# AnalogInputModule2_r1_0.net
KiCad netlist of a schematic drawn in EAGLE
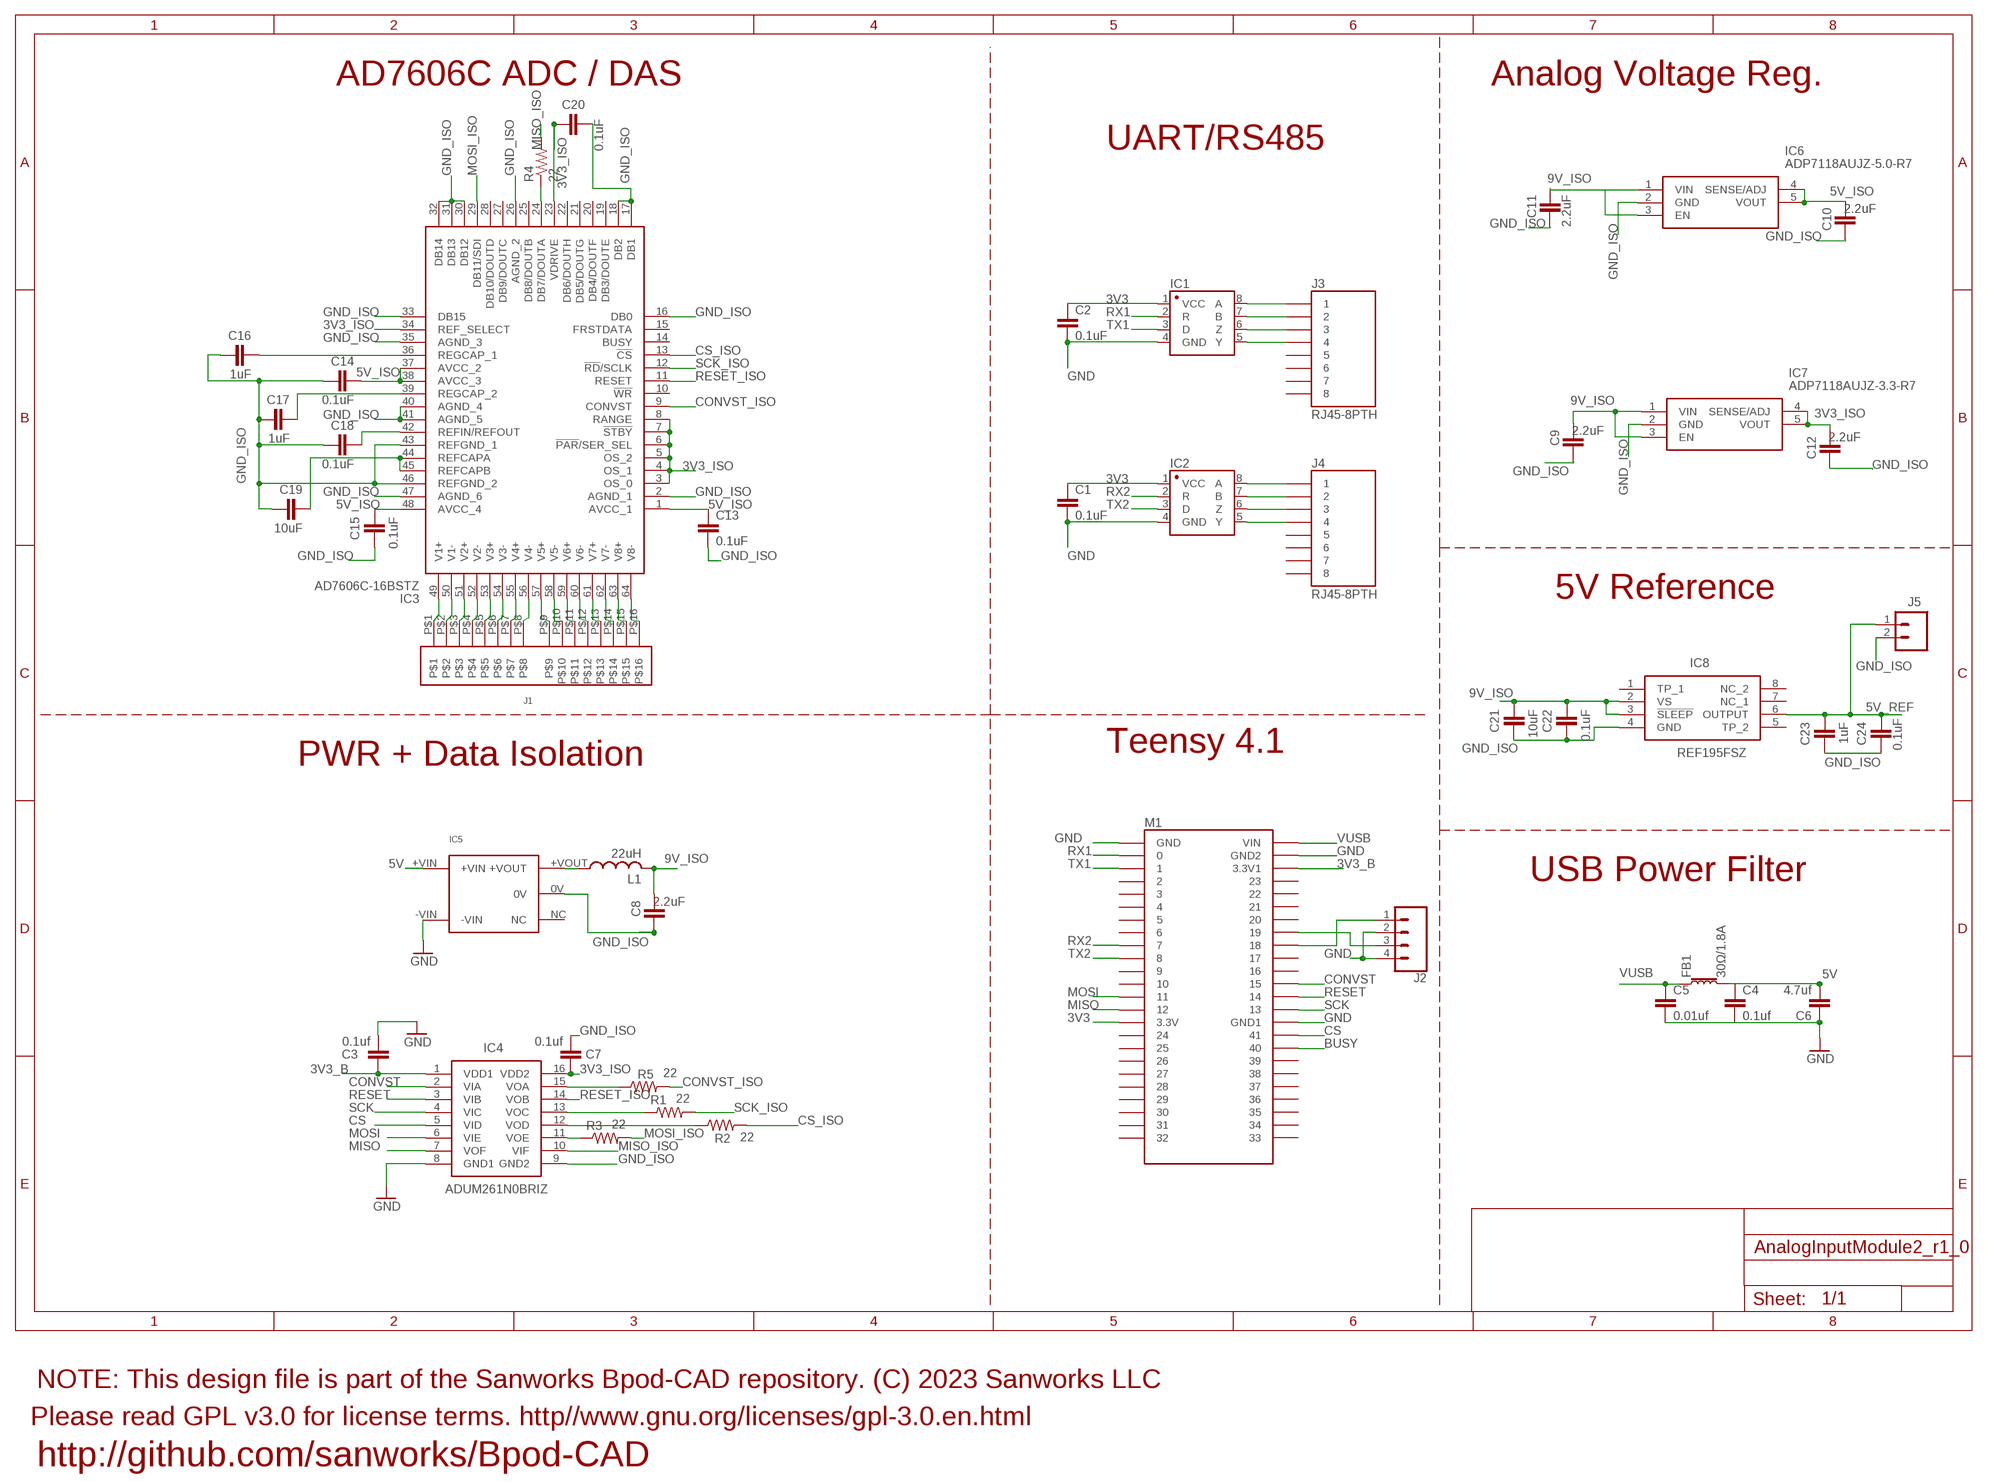
[diagram p0: schematic, sheet 1]

(export (version "E")
  (design (tool "Eeschema 10.0.6"))
  (components
    (comp (ref "C1")
      (value "0.1uF")
      (footprint "eagle-import:0805")
      (libsource (lib "eagle-import") (part "1.0UF-0805-25V-10%"))
    )
    (comp (ref "C2")
      (value "0.1uF")
      (footprint "eagle-import:0805")
      (libsource (lib "eagle-import") (part "1.0UF-0805-25V-10%"))
    )
    (comp (ref "C3")
      (value "0.1uf")
      (footprint "eagle-import:0805")
      (libsource (lib "eagle-import") (part "1.0UF-0805-25V-10%"))
    )
    (comp (ref "C4")
      (value "0.1uf")
      (footprint "eagle-import:0805")
      (libsource (lib "eagle-import") (part "10UF-0805-10V-10%"))
    )
    (comp (ref "C5")
      (value "0.01uf")
      (footprint "eagle-import:0805")
      (libsource (lib "eagle-import") (part "10UF-0805-10V-10%"))
    )
    (comp (ref "C6")
      (value "4.7uf")
      (footprint "eagle-import:1206@2")
      (libsource (lib "eagle-import") (part "CAP1206"))
    )
    (comp (ref "C7")
      (value "0.1uf")
      (footprint "eagle-import:0805")
      (libsource (lib "eagle-import") (part "1.0UF-0805-25V-10%"))
    )
    (comp (ref "C8")
      (value "2.2uF")
      (footprint "eagle-import:0805")
      (libsource (lib "eagle-import") (part "1.0UF-0805-25V-(+80/-20%)"))
    )
    (comp (ref "C9")
      (value "2.2uF")
      (footprint "eagle-import:0805")
      (libsource (lib "eagle-import") (part "1.0UF-0805-25V-(+80/-20%)"))
    )
    (comp (ref "C10")
      (value "2.2uF")
      (footprint "eagle-import:0805")
      (libsource (lib "eagle-import") (part "1.0UF-0805-25V-(+80/-20%)"))
    )
    (comp (ref "C11")
      (value "2.2uF")
      (footprint "eagle-import:0805")
      (libsource (lib "eagle-import") (part "1.0UF-0805-25V-(+80/-20%)"))
    )
    (comp (ref "C12")
      (value "2.2uF")
      (footprint "eagle-import:0805")
      (libsource (lib "eagle-import") (part "1.0UF-0805-25V-(+80/-20%)"))
    )
    (comp (ref "C13")
      (value "0.1uF")
      (footprint "eagle-import:0805")
      (libsource (lib "eagle-import") (part "1.0UF-0805-25V-10%"))
    )
    (comp (ref "C14")
      (value "0.1uF")
      (footprint "eagle-import:0805")
      (libsource (lib "eagle-import") (part "1.0UF-0805-25V-10%"))
    )
    (comp (ref "C15")
      (value "0.1uF")
      (footprint "eagle-import:0805")
      (libsource (lib "eagle-import") (part "1.0UF-0805-25V-10%"))
    )
    (comp (ref "C16")
      (value "1uF")
      (footprint "eagle-import:0805")
      (libsource (lib "eagle-import") (part "1.0UF-0805-25V-10%"))
    )
    (comp (ref "C17")
      (value "1uF")
      (footprint "eagle-import:0805")
      (libsource (lib "eagle-import") (part "1.0UF-0805-25V-10%"))
    )
    (comp (ref "C18")
      (value "0.1uF")
      (footprint "eagle-import:0805")
      (libsource (lib "eagle-import") (part "1.0UF-0805-25V-10%"))
    )
    (comp (ref "C19")
      (value "10uF")
      (footprint "eagle-import:0805")
      (libsource (lib "eagle-import") (part "1.0UF-0805-25V-10%"))
    )
    (comp (ref "C20")
      (value "0.1uF")
      (footprint "eagle-import:0805")
      (libsource (lib "eagle-import") (part "1.0UF-0805-25V-10%"))
    )
    (comp (ref "C21")
      (value "10uF")
      (footprint "eagle-import:0805")
      (libsource (lib "eagle-import") (part "1.0UF-0805-25V-10%"))
    )
    (comp (ref "C22")
      (value "0.1uF")
      (footprint "eagle-import:0805")
      (libsource (lib "eagle-import") (part "1.0UF-0805-25V-10%"))
    )
    (comp (ref "C23")
      (value "1uF")
      (footprint "eagle-import:0805")
      (libsource (lib "eagle-import") (part "1.0UF-0805-25V-10%"))
    )
    (comp (ref "C24")
      (value "0.1uF")
      (footprint "eagle-import:0805")
      (libsource (lib "eagle-import") (part "1.0UF-0805-25V-10%"))
    )
    (comp (ref "FB1")
      (value "30Ω/1.8A")
      (footprint "eagle-import:0603")
      (libsource (lib "eagle-import") (part "FERRITE_BEAD-0603"))
    )
    (comp (ref "IC1")
      (value "SN65HVD31DR")
      (footprint "eagle-import:SO08")
      (libsource (lib "eagle-import") (part "SN65HVD31DR"))
    )
    (comp (ref "IC2")
      (value "SN65HVD31DR")
      (footprint "eagle-import:SO08")
      (libsource (lib "eagle-import") (part "SN65HVD31DR"))
    )
    (comp (ref "IC3")
      (value "AD7606C-16BSTZ")
      (footprint "eagle-import:QFP50P1200X1200X160-64N")
      (fields (field (name "MOUSER_PART_NUMBER") "584-AD7606C-16BSTZ"))
      (libsource (lib "eagle-import") (part "AD7606C-16BSTZ"))
    )
    (comp (ref "IC4")
      (value "ADUM261N0BRIZ")
      (footprint "eagle-import:SOIC127P1030X264-16N")
      (fields (field (name "MOUSER_PART_NUMBER") "584-ADUM261N0BRIZ"))
      (libsource (lib "eagle-import") (part "ADUM261N0BRIZ"))
    )
    (comp (ref "IC5")
      (value "5V")
      (footprint "eagle-import:MTU1D0505MC")
      (libsource (lib "eagle-import") (part "MTU1D0505MC"))
    )
    (comp (ref "IC6")
      (value "ADP7118AUJZ-5.0-R7")
      (footprint "eagle-import:SOT95P280X100-5N")
      (fields (field (name "MOUSER_PART_NUMBER") "584-ADP7118AUJZ5.0R7"))
      (libsource (lib "eagle-import") (part "ADP7118AUJZ-5.0-R7"))
    )
    (comp (ref "IC7")
      (value "ADP7118AUJZ-3.3-R7")
      (footprint "eagle-import:SOT95P280X100-5N")
      (fields (field (name "MOUSER_PART_NUMBER") "584-ADP7118AUJZ3.3R7"))
      (libsource (lib "eagle-import") (part "ADP7118AUJZ-3.3-R7"))
    )
    (comp (ref "IC8")
      (value "REF195FSZ")
      (footprint "eagle-import:SOIC127P600X175-8N")
      (fields (field (name "MOUSER_PART_NUMBER") "584-REF195FSZ"))
      (libsource (lib "eagle-import") (part "REF195FSZ"))
    )
    (comp (ref "J1")
      (value "16POS_MOLEX_SOCKET")
      (footprint "eagle-import:16POS_MOLEX_SOCKET")
      (libsource (lib "eagle-import") (part "16POS_MOLEX_SOCKET"))
    )
    (comp (ref "J2")
      (value "CONN_04SCREW_LOCK")
      (footprint "eagle-import:SCREWTERMINAL-3.5MM-4_LOCK")
      (libsource (lib "eagle-import") (part "CONN_04SCREW_LOCK"))
    )
    (comp (ref "J3")
      (value "RJ45-8PTH")
      (footprint "eagle-import:RJ45-8")
      (libsource (lib "eagle-import") (part "RJ45-8PTH"))
    )
    (comp (ref "J4")
      (value "RJ45-8PTH")
      (footprint "eagle-import:RJ45-8")
      (libsource (lib "eagle-import") (part "RJ45-8PTH"))
    )
    (comp (ref "J5")
      (value "CONN_023.5MM_LOCK")
      (footprint "eagle-import:SCREWTERMINAL-3.5MM-2_LOCK")
      (libsource (lib "eagle-import") (part "CONN_023.5MM_LOCK"))
    )
    (comp (ref "L1")
      (value "22uH")
      (footprint "eagle-import:L3225M")
      (libsource (lib "eagle-import") (part "L-USL3225M"))
    )
    (comp (ref "M1")
      (value "TEENSY4.1_SIDESONLY")
      (footprint "eagle-import:TEENSY4.1_SIDESONLY")
      (libsource (lib "eagle-import") (part "TEENSY4.1_SIDESONLY"))
    )
    (comp (ref "R1")
      (value "22")
      (footprint "eagle-import:R0805")
      (libsource (lib "eagle-import") (part "R-US_R0805"))
    )
    (comp (ref "R2")
      (value "22")
      (footprint "eagle-import:R0805")
      (libsource (lib "eagle-import") (part "R-US_R0805"))
    )
    (comp (ref "R3")
      (value "22")
      (footprint "eagle-import:R0805")
      (libsource (lib "eagle-import") (part "R-US_R0805"))
    )
    (comp (ref "R4")
      (value "22")
      (footprint "eagle-import:R0805")
      (libsource (lib "eagle-import") (part "R-US_R0805"))
    )
    (comp (ref "R5")
      (value "22")
      (footprint "eagle-import:R0805")
      (libsource (lib "eagle-import") (part "R-US_R0805"))
    )
  )
  (nets
    (net (code "1") (name "/3V3") (class "Default")
      (node (ref "C1") (pin "1") (pinfunction "1_1") (pintype "passive"))
      (node (ref "C2") (pin "1") (pinfunction "1_1") (pintype "passive"))
      (node (ref "IC1") (pin "1") (pinfunction "VCC_1") (pintype "bidirectional"))
      (node (ref "IC2") (pin "1") (pinfunction "VCC_1") (pintype "bidirectional"))
      (node (ref "M1") (pin "3V3") (pinfunction "3.3V_3V3") (pintype "bidirectional"))
    )
    (net (code "2") (name "/3V3_B") (class "Default")
      (node (ref "C3") (pin "1") (pinfunction "1_1") (pintype "passive"))
      (node (ref "IC4") (pin "1") (pinfunction "VDD1_1") (pintype "bidirectional"))
      (node (ref "M1") (pin "3V3_LO") (pinfunction "3.3V1_3V3_LO") (pintype "bidirectional"))
    )
    (net (code "3") (name "/3V3_ISO") (class "Default")
      (node (ref "C12") (pin "2") (pinfunction "2_2") (pintype "passive"))
      (node (ref "C20") (pin "1") (pinfunction "1_1") (pintype "passive"))
      (node (ref "C7") (pin "1") (pinfunction "1_1") (pintype "passive"))
      (node (ref "IC3") (pin "23") (pinfunction "VDRIVE_23") (pintype "bidirectional"))
      (node (ref "IC3") (pin "3") (pinfunction "OS_0_3") (pintype "bidirectional"))
      (node (ref "IC3") (pin "34") (pinfunction "REF_SELECT_34") (pintype "bidirectional"))
      (node (ref "IC3") (pin "4") (pinfunction "OS_1_4") (pintype "bidirectional"))
      (node (ref "IC3") (pin "5") (pinfunction "OS_2_5") (pintype "bidirectional"))
      (node (ref "IC3") (pin "6") (pinfunction "~{PAR}/SER_SEL_6") (pintype "bidirectional"))
      (node (ref "IC3") (pin "7") (pinfunction "~{STBY}_7") (pintype "bidirectional"))
      (node (ref "IC3") (pin "8") (pinfunction "RANGE_8") (pintype "bidirectional"))
      (node (ref "IC4") (pin "16") (pinfunction "VDD2_16") (pintype "bidirectional"))
      (node (ref "IC7") (pin "4") (pinfunction "SENSE/ADJ_4") (pintype "bidirectional"))
      (node (ref "IC7") (pin "5") (pinfunction "VOUT_5") (pintype "bidirectional"))
    )
    (net (code "4") (name "/5V") (class "Default")
      (node (ref "C4") (pin "1") (pinfunction "1_1") (pintype "passive"))
      (node (ref "C6") (pin "2") (pinfunction "2_2") (pintype "passive"))
      (node (ref "FB1") (pin "2") (pinfunction "2_2") (pintype "passive"))
      (node (ref "IC5") (pin "+VIN") (pinfunction "+VIN_+VIN") (pintype "bidirectional"))
    )
    (net (code "5") (name "/5V_ISO") (class "Default")
      (node (ref "C10") (pin "2") (pinfunction "2_2") (pintype "passive"))
      (node (ref "C13") (pin "1") (pinfunction "1_1") (pintype "passive"))
      (node (ref "C14") (pin "2") (pinfunction "2_2") (pintype "passive"))
      (node (ref "C15") (pin "2") (pinfunction "2_2") (pintype "passive"))
      (node (ref "IC3") (pin "1") (pinfunction "AVCC_1_1") (pintype "bidirectional"))
      (node (ref "IC3") (pin "37") (pinfunction "AVCC_2_37") (pintype "bidirectional"))
      (node (ref "IC3") (pin "38") (pinfunction "AVCC_3_38") (pintype "bidirectional"))
      (node (ref "IC3") (pin "48") (pinfunction "AVCC_4_48") (pintype "bidirectional"))
      (node (ref "IC6") (pin "4") (pinfunction "SENSE/ADJ_4") (pintype "bidirectional"))
      (node (ref "IC6") (pin "5") (pinfunction "VOUT_5") (pintype "bidirectional"))
    )
    (net (code "6") (name "/5V_REF") (class "Default")
      (node (ref "C23") (pin "2") (pinfunction "2_2") (pintype "passive"))
      (node (ref "C24") (pin "2") (pinfunction "2_2") (pintype "passive"))
      (node (ref "IC8") (pin "6") (pinfunction "OUTPUT_6") (pintype "bidirectional"))
      (node (ref "J5") (pin "1") (pinfunction "1_1") (pintype "passive"))
    )
    (net (code "7") (name "/9V_ISO") (class "Default")
      (node (ref "C11") (pin "2") (pinfunction "2_2") (pintype "passive"))
      (node (ref "C21") (pin "2") (pinfunction "2_2") (pintype "passive"))
      (node (ref "C22") (pin "2") (pinfunction "2_2") (pintype "passive"))
      (node (ref "C8") (pin "2") (pinfunction "2_2") (pintype "passive"))
      (node (ref "C9") (pin "2") (pinfunction "2_2") (pintype "passive"))
      (node (ref "IC6") (pin "1") (pinfunction "VIN_1") (pintype "bidirectional"))
      (node (ref "IC6") (pin "3") (pinfunction "EN_3") (pintype "bidirectional"))
      (node (ref "IC7") (pin "1") (pinfunction "VIN_1") (pintype "bidirectional"))
      (node (ref "IC7") (pin "3") (pinfunction "EN_3") (pintype "bidirectional"))
      (node (ref "IC8") (pin "2") (pinfunction "VS_2") (pintype "bidirectional"))
      (node (ref "IC8") (pin "3") (pinfunction "~{SLEEP}_3") (pintype "bidirectional"))
      (node (ref "L1") (pin "2") (pinfunction "2_2") (pintype "passive"))
    )
    (net (code "8") (name "/BUSY") (class "Default")
      (node (ref "M1") (pin "40") (pinfunction "40_40") (pintype "bidirectional"))
    )
    (net (code "9") (name "/CONVST") (class "Default")
      (node (ref "IC4") (pin "2") (pinfunction "VIA_2") (pintype "bidirectional"))
      (node (ref "M1") (pin "15/A1") (pinfunction "15_15/A1") (pintype "bidirectional"))
    )
    (net (code "10") (name "/CONVST_ISO") (class "Default")
      (node (ref "IC3") (pin "9") (pinfunction "CONVST_9") (pintype "bidirectional"))
      (node (ref "R5") (pin "2") (pinfunction "2_2") (pintype "passive"))
    )
    (net (code "11") (name "/CS") (class "Default")
      (node (ref "IC4") (pin "5") (pinfunction "VID_5") (pintype "bidirectional"))
      (node (ref "M1") (pin "41") (pinfunction "41_41") (pintype "bidirectional"))
    )
    (net (code "12") (name "/CS_ISO") (class "Default")
      (node (ref "IC3") (pin "13") (pinfunction "~{CS}_13") (pintype "bidirectional"))
      (node (ref "R2") (pin "2") (pinfunction "2_2") (pintype "passive"))
    )
    (net (code "13") (name "/GND_ISO") (class "Default")
      (node (ref "C10") (pin "1") (pinfunction "1_1") (pintype "passive"))
      (node (ref "C11") (pin "1") (pinfunction "1_1") (pintype "passive"))
      (node (ref "C12") (pin "1") (pinfunction "1_1") (pintype "passive"))
      (node (ref "C13") (pin "2") (pinfunction "2_2") (pintype "passive"))
      (node (ref "C14") (pin "1") (pinfunction "1_1") (pintype "passive"))
      (node (ref "C15") (pin "1") (pinfunction "1_1") (pintype "passive"))
      (node (ref "C16") (pin "1") (pinfunction "1_1") (pintype "passive"))
      (node (ref "C17") (pin "1") (pinfunction "1_1") (pintype "passive"))
      (node (ref "C18") (pin "1") (pinfunction "1_1") (pintype "passive"))
      (node (ref "C19") (pin "1") (pinfunction "1_1") (pintype "passive"))
      (node (ref "C20") (pin "2") (pinfunction "2_2") (pintype "passive"))
      (node (ref "C21") (pin "1") (pinfunction "1_1") (pintype "passive"))
      (node (ref "C22") (pin "1") (pinfunction "1_1") (pintype "passive"))
      (node (ref "C23") (pin "1") (pinfunction "1_1") (pintype "passive"))
      (node (ref "C24") (pin "1") (pinfunction "1_1") (pintype "passive"))
      (node (ref "C7") (pin "2") (pinfunction "2_2") (pintype "passive"))
      (node (ref "C8") (pin "1") (pinfunction "1_1") (pintype "passive"))
      (node (ref "C9") (pin "1") (pinfunction "1_1") (pintype "passive"))
      (node (ref "IC3") (pin "16") (pinfunction "DB0_16") (pintype "bidirectional"))
      (node (ref "IC3") (pin "17") (pinfunction "DB1_17") (pintype "bidirectional"))
      (node (ref "IC3") (pin "18") (pinfunction "DB2_18") (pintype "bidirectional"))
      (node (ref "IC3") (pin "2") (pinfunction "AGND_1_2") (pintype "bidirectional"))
      (node (ref "IC3") (pin "26") (pinfunction "AGND_2_26") (pintype "bidirectional"))
      (node (ref "IC3") (pin "30") (pinfunction "DB12_30") (pintype "bidirectional"))
      (node (ref "IC3") (pin "31") (pinfunction "DB13_31") (pintype "bidirectional"))
      (node (ref "IC3") (pin "32") (pinfunction "DB14_32") (pintype "bidirectional"))
      (node (ref "IC3") (pin "33") (pinfunction "DB15_33") (pintype "bidirectional"))
      (node (ref "IC3") (pin "35") (pinfunction "AGND_3_35") (pintype "bidirectional"))
      (node (ref "IC3") (pin "40") (pinfunction "AGND_4_40") (pintype "bidirectional"))
      (node (ref "IC3") (pin "41") (pinfunction "AGND_5_41") (pintype "bidirectional"))
      (node (ref "IC3") (pin "43") (pinfunction "REFGND_1_43") (pintype "bidirectional"))
      (node (ref "IC3") (pin "46") (pinfunction "REFGND_2_46") (pintype "bidirectional"))
      (node (ref "IC3") (pin "47") (pinfunction "AGND_6_47") (pintype "bidirectional"))
      (node (ref "IC4") (pin "9") (pinfunction "GND2_9") (pintype "bidirectional"))
      (node (ref "IC5") (pin "0V") (pinfunction "0V_0V") (pintype "bidirectional"))
      (node (ref "IC6") (pin "2") (pinfunction "GND_2") (pintype "bidirectional"))
      (node (ref "IC7") (pin "2") (pinfunction "GND_2") (pintype "bidirectional"))
      (node (ref "IC8") (pin "4") (pinfunction "GND_4") (pintype "bidirectional"))
      (node (ref "J5") (pin "2") (pinfunction "2_2") (pintype "passive"))
    )
    (net (code "14") (name "/MISO") (class "Default")
      (node (ref "IC4") (pin "7") (pinfunction "VOF_7") (pintype "bidirectional"))
      (node (ref "M1") (pin "12/MISO") (pinfunction "12_12/MISO") (pintype "bidirectional"))
    )
    (net (code "15") (name "/MISO_ISO") (class "Default")
      (node (ref "IC4") (pin "10") (pinfunction "VIF_10") (pintype "bidirectional"))
      (node (ref "R4") (pin "2") (pinfunction "2_2") (pintype "passive"))
    )
    (net (code "16") (name "/MOSI") (class "Default")
      (node (ref "IC4") (pin "6") (pinfunction "VIE_6") (pintype "bidirectional"))
      (node (ref "M1") (pin "11/MOSI") (pinfunction "11_11/MOSI") (pintype "bidirectional"))
    )
    (net (code "17") (name "/MOSI_ISO") (class "Default")
      (node (ref "IC3") (pin "29") (pinfunction "DB11/SDI_29") (pintype "bidirectional"))
      (node (ref "R3") (pin "2") (pinfunction "2_2") (pintype "passive"))
    )
    (net (code "18") (name "/RESET") (class "Default")
      (node (ref "IC4") (pin "3") (pinfunction "VIB_3") (pintype "bidirectional"))
      (node (ref "M1") (pin "14/A0") (pinfunction "14_14/A0") (pintype "bidirectional"))
    )
    (net (code "19") (name "/RESET_ISO") (class "Default")
      (node (ref "IC3") (pin "11") (pinfunction "RESET_11") (pintype "bidirectional"))
      (node (ref "IC4") (pin "14") (pinfunction "VOB_14") (pintype "bidirectional"))
    )
    (net (code "20") (name "/RX1") (class "Default")
      (node (ref "IC1") (pin "2") (pinfunction "R_2") (pintype "bidirectional"))
      (node (ref "M1") (pin "0/RX") (pinfunction "0_0/RX") (pintype "bidirectional"))
    )
    (net (code "21") (name "/RX2") (class "Default")
      (node (ref "IC2") (pin "2") (pinfunction "R_2") (pintype "bidirectional"))
      (node (ref "M1") (pin "7") (pinfunction "7_7") (pintype "bidirectional"))
    )
    (net (code "22") (name "/SCK") (class "Default")
      (node (ref "IC4") (pin "4") (pinfunction "VIC_4") (pintype "bidirectional"))
      (node (ref "M1") (pin "13/SCK") (pinfunction "13_13/SCK") (pintype "bidirectional"))
    )
    (net (code "23") (name "/SCK_ISO") (class "Default")
      (node (ref "IC3") (pin "12") (pinfunction "~{RD}/SCLK_12") (pintype "bidirectional"))
      (node (ref "R1") (pin "2") (pinfunction "2_2") (pintype "passive"))
    )
    (net (code "24") (name "/TX1") (class "Default")
      (node (ref "IC1") (pin "3") (pinfunction "D_3") (pintype "bidirectional"))
      (node (ref "M1") (pin "1/TX") (pinfunction "1_1/TX") (pintype "bidirectional"))
    )
    (net (code "25") (name "/TX2") (class "Default")
      (node (ref "IC2") (pin "3") (pinfunction "D_3") (pintype "bidirectional"))
      (node (ref "M1") (pin "8") (pinfunction "8_8") (pintype "bidirectional"))
    )
    (net (code "26") (name "/VUSB") (class "Default")
      (node (ref "C5") (pin "1") (pinfunction "1_1") (pintype "passive"))
      (node (ref "FB1") (pin "1") (pinfunction "1_1") (pintype "passive"))
      (node (ref "M1") (pin "VIN") (pinfunction "VIN_VIN") (pintype "bidirectional"))
    )
    (net (code "27") (name "GND") (class "Default")
      (node (ref "C1") (pin "2") (pinfunction "2_2") (pintype "passive"))
      (node (ref "C2") (pin "2") (pinfunction "2_2") (pintype "passive"))
      (node (ref "C3") (pin "2") (pinfunction "2_2") (pintype "passive"))
      (node (ref "C4") (pin "2") (pinfunction "2_2") (pintype "passive"))
      (node (ref "C5") (pin "2") (pinfunction "2_2") (pintype "passive"))
      (node (ref "C6") (pin "1") (pinfunction "1_1") (pintype "passive"))
      (node (ref "IC1") (pin "4") (pinfunction "GND_4") (pintype "bidirectional"))
      (node (ref "IC2") (pin "4") (pinfunction "GND_4") (pintype "bidirectional"))
      (node (ref "IC4") (pin "8") (pinfunction "GND1_8") (pintype "bidirectional"))
      (node (ref "IC5") (pin "-VIN") (pinfunction "-VIN_-VIN") (pintype "bidirectional"))
      (node (ref "J2") (pin "2") (pinfunction "2_2") (pintype "passive"))
      (node (ref "J2") (pin "4") (pinfunction "4_4") (pintype "passive"))
      (node (ref "M1") (pin "AGND") (pinfunction "GND_AGND") (pintype "bidirectional"))
      (node (ref "M1") (pin "GND") (pinfunction "GND1_GND") (pintype "bidirectional"))
      (node (ref "M1") (pin "GND1") (pinfunction "GND2_GND1") (pintype "bidirectional"))
    )
    (net (code "28") (name "Net-(IC1-A)") (class "Default")
      (node (ref "IC1") (pin "8") (pinfunction "A_8") (pintype "bidirectional"))
      (node (ref "J3") (pin "1") (pinfunction "1_1") (pintype "bidirectional"))
    )
    (net (code "29") (name "Net-(IC1-B)") (class "Default")
      (node (ref "IC1") (pin "7") (pinfunction "B_7") (pintype "bidirectional"))
      (node (ref "J3") (pin "2") (pinfunction "2_2") (pintype "bidirectional"))
    )
    (net (code "30") (name "Net-(IC1-Y)") (class "Default")
      (node (ref "IC1") (pin "5") (pinfunction "Y_5") (pintype "bidirectional"))
      (node (ref "J3") (pin "4") (pinfunction "4_4") (pintype "bidirectional"))
    )
    (net (code "31") (name "Net-(IC1-Z)") (class "Default")
      (node (ref "IC1") (pin "6") (pinfunction "Z_6") (pintype "bidirectional"))
      (node (ref "J3") (pin "3") (pinfunction "3_3") (pintype "bidirectional"))
    )
    (net (code "32") (name "Net-(IC2-A)") (class "Default")
      (node (ref "IC2") (pin "8") (pinfunction "A_8") (pintype "bidirectional"))
      (node (ref "J4") (pin "1") (pinfunction "1_1") (pintype "bidirectional"))
    )
    (net (code "33") (name "Net-(IC2-B)") (class "Default")
      (node (ref "IC2") (pin "7") (pinfunction "B_7") (pintype "bidirectional"))
      (node (ref "J4") (pin "2") (pinfunction "2_2") (pintype "bidirectional"))
    )
    (net (code "34") (name "Net-(IC2-Y)") (class "Default")
      (node (ref "IC2") (pin "5") (pinfunction "Y_5") (pintype "bidirectional"))
      (node (ref "J4") (pin "4") (pinfunction "4_4") (pintype "bidirectional"))
    )
    (net (code "35") (name "Net-(IC2-Z)") (class "Default")
      (node (ref "IC2") (pin "6") (pinfunction "Z_6") (pintype "bidirectional"))
      (node (ref "J4") (pin "3") (pinfunction "3_3") (pintype "bidirectional"))
    )
    (net (code "36") (name "Net-(IC3-DB7{slash}DOUTA)") (class "Default")
      (node (ref "IC3") (pin "24") (pinfunction "DB7/DOUTA_24") (pintype "bidirectional"))
      (node (ref "R4") (pin "1") (pinfunction "1_1") (pintype "passive"))
    )
    (net (code "37") (name "Net-(IC3-REFCAPA)") (class "Default")
      (node (ref "C19") (pin "2") (pinfunction "2_2") (pintype "passive"))
      (node (ref "IC3") (pin "44") (pinfunction "REFCAPA_44") (pintype "bidirectional"))
      (node (ref "IC3") (pin "45") (pinfunction "REFCAPB_45") (pintype "bidirectional"))
    )
    (net (code "38") (name "Net-(IC3-REFIN{slash}REFOUT)") (class "Default")
      (node (ref "C18") (pin "2") (pinfunction "2_2") (pintype "passive"))
      (node (ref "IC3") (pin "42") (pinfunction "REFIN/REFOUT_42") (pintype "bidirectional"))
    )
    (net (code "39") (name "Net-(IC3-REGCAP_1)") (class "Default")
      (node (ref "C16") (pin "2") (pinfunction "2_2") (pintype "passive"))
      (node (ref "IC3") (pin "36") (pinfunction "REGCAP_1_36") (pintype "bidirectional"))
    )
    (net (code "40") (name "Net-(IC3-REGCAP_2)") (class "Default")
      (node (ref "C17") (pin "2") (pinfunction "2_2") (pintype "passive"))
      (node (ref "IC3") (pin "39") (pinfunction "REGCAP_2_39") (pintype "bidirectional"))
    )
    (net (code "41") (name "Net-(IC3-V1+)") (class "Default")
      (node (ref "IC3") (pin "49") (pinfunction "V1+_49") (pintype "bidirectional"))
      (node (ref "J1") (pin "P$1") (pinfunction "P$1_P$1") (pintype "bidirectional"))
    )
    (net (code "42") (name "Net-(IC3-V1-)") (class "Default")
      (node (ref "IC3") (pin "50") (pinfunction "V1-_50") (pintype "bidirectional"))
      (node (ref "J1") (pin "P$2") (pinfunction "P$2_P$2") (pintype "bidirectional"))
    )
    (net (code "43") (name "Net-(IC3-V2+)") (class "Default")
      (node (ref "IC3") (pin "51") (pinfunction "V2+_51") (pintype "bidirectional"))
      (node (ref "J1") (pin "P$3") (pinfunction "P$3_P$3") (pintype "bidirectional"))
    )
    (net (code "44") (name "Net-(IC3-V2-)") (class "Default")
      (node (ref "IC3") (pin "52") (pinfunction "V2-_52") (pintype "bidirectional"))
      (node (ref "J1") (pin "P$4") (pinfunction "P$4_P$4") (pintype "bidirectional"))
    )
    (net (code "45") (name "Net-(IC3-V3+)") (class "Default")
      (node (ref "IC3") (pin "53") (pinfunction "V3+_53") (pintype "bidirectional"))
      (node (ref "J1") (pin "P$5") (pinfunction "P$5_P$5") (pintype "bidirectional"))
    )
    (net (code "46") (name "Net-(IC3-V3-)") (class "Default")
      (node (ref "IC3") (pin "54") (pinfunction "V3-_54") (pintype "bidirectional"))
      (node (ref "J1") (pin "P$6") (pinfunction "P$6_P$6") (pintype "bidirectional"))
    )
    (net (code "47") (name "Net-(IC3-V4+)") (class "Default")
      (node (ref "IC3") (pin "55") (pinfunction "V4+_55") (pintype "bidirectional"))
      (node (ref "J1") (pin "P$7") (pinfunction "P$7_P$7") (pintype "bidirectional"))
    )
    (net (code "48") (name "Net-(IC3-V4-)") (class "Default")
      (node (ref "IC3") (pin "56") (pinfunction "V4-_56") (pintype "bidirectional"))
      (node (ref "J1") (pin "P$8") (pinfunction "P$8_P$8") (pintype "bidirectional"))
    )
    (net (code "49") (name "Net-(IC3-V5+)") (class "Default")
      (node (ref "IC3") (pin "57") (pinfunction "V5+_57") (pintype "bidirectional"))
      (node (ref "J1") (pin "P$9") (pinfunction "P$9_P$9") (pintype "bidirectional"))
    )
    (net (code "50") (name "Net-(IC3-V5-)") (class "Default")
      (node (ref "IC3") (pin "58") (pinfunction "V5-_58") (pintype "bidirectional"))
      (node (ref "J1") (pin "P$10") (pinfunction "P$10_P$10") (pintype "bidirectional"))
    )
    (net (code "51") (name "Net-(IC3-V6+)") (class "Default")
      (node (ref "IC3") (pin "59") (pinfunction "V6+_59") (pintype "bidirectional"))
      (node (ref "J1") (pin "P$11") (pinfunction "P$11_P$11") (pintype "bidirectional"))
    )
    (net (code "52") (name "Net-(IC3-V6-)") (class "Default")
      (node (ref "IC3") (pin "60") (pinfunction "V6-_60") (pintype "bidirectional"))
      (node (ref "J1") (pin "P$12") (pinfunction "P$12_P$12") (pintype "bidirectional"))
    )
    (net (code "53") (name "Net-(IC3-V7+)") (class "Default")
      (node (ref "IC3") (pin "61") (pinfunction "V7+_61") (pintype "bidirectional"))
      (node (ref "J1") (pin "P$13") (pinfunction "P$13_P$13") (pintype "bidirectional"))
    )
    (net (code "54") (name "Net-(IC3-V7-)") (class "Default")
      (node (ref "IC3") (pin "62") (pinfunction "V7-_62") (pintype "bidirectional"))
      (node (ref "J1") (pin "P$14") (pinfunction "P$14_P$14") (pintype "bidirectional"))
    )
    (net (code "55") (name "Net-(IC3-V8+)") (class "Default")
      (node (ref "IC3") (pin "63") (pinfunction "V8+_63") (pintype "bidirectional"))
      (node (ref "J1") (pin "P$15") (pinfunction "P$15_P$15") (pintype "bidirectional"))
    )
    (net (code "56") (name "Net-(IC3-V8-)") (class "Default")
      (node (ref "IC3") (pin "64") (pinfunction "V8-_64") (pintype "bidirectional"))
      (node (ref "J1") (pin "P$16") (pinfunction "P$16_P$16") (pintype "bidirectional"))
    )
    (net (code "57") (name "Net-(IC4-VOA)") (class "Default")
      (node (ref "IC4") (pin "15") (pinfunction "VOA_15") (pintype "bidirectional"))
      (node (ref "R5") (pin "1") (pinfunction "1_1") (pintype "passive"))
    )
    (net (code "58") (name "Net-(IC4-VOC)") (class "Default")
      (node (ref "IC4") (pin "13") (pinfunction "VOC_13") (pintype "bidirectional"))
      (node (ref "R1") (pin "1") (pinfunction "1_1") (pintype "passive"))
    )
    (net (code "59") (name "Net-(IC4-VOD)") (class "Default")
      (node (ref "IC4") (pin "12") (pinfunction "VOD_12") (pintype "bidirectional"))
      (node (ref "R2") (pin "1") (pinfunction "1_1") (pintype "passive"))
    )
    (net (code "60") (name "Net-(IC4-VOE)") (class "Default")
      (node (ref "IC4") (pin "11") (pinfunction "VOE_11") (pintype "bidirectional"))
      (node (ref "R3") (pin "1") (pinfunction "1_1") (pintype "passive"))
    )
    (net (code "61") (name "Net-(IC5-Pad+VOUT)") (class "Default")
      (node (ref "IC5") (pin "+VOUT") (pinfunction "+VOUT_+VOUT") (pintype "bidirectional"))
      (node (ref "L1") (pin "1") (pinfunction "1_1") (pintype "passive"))
    )
    (net (code "62") (name "Net-(M1-18)") (class "Default")
      (node (ref "J2") (pin "1") (pinfunction "1_1") (pintype "passive"))
      (node (ref "M1") (pin "18/A4/SDA") (pinfunction "18_18/A4/SDA") (pintype "bidirectional"))
    )
    (net (code "63") (name "Net-(M1-19)") (class "Default")
      (node (ref "J2") (pin "3") (pinfunction "3_3") (pintype "passive"))
      (node (ref "M1") (pin "19/A5/SCL") (pinfunction "19_19/A5/SCL") (pintype "bidirectional"))
    )
    (net (code "64") (name "unconnected-(IC3-BUSY-Pad14)") (class "Default")
      (node (ref "IC3") (pin "14") (pinfunction "BUSY_14") (pintype "bidirectional"))
    )
    (net (code "65") (name "unconnected-(IC3-DB3{slash}DOUTE-Pad19)") (class "Default")
      (node (ref "IC3") (pin "19") (pinfunction "DB3/DOUTE_19") (pintype "bidirectional"))
    )
    (net (code "66") (name "unconnected-(IC3-DB4{slash}DOUTF-Pad20)") (class "Default")
      (node (ref "IC3") (pin "20") (pinfunction "DB4/DOUTF_20") (pintype "bidirectional"))
    )
    (net (code "67") (name "unconnected-(IC3-DB5{slash}DOUTG-Pad21)") (class "Default")
      (node (ref "IC3") (pin "21") (pinfunction "DB5/DOUTG_21") (pintype "bidirectional"))
    )
    (net (code "68") (name "unconnected-(IC3-DB6{slash}DOUTH-Pad22)") (class "Default")
      (node (ref "IC3") (pin "22") (pinfunction "DB6/DOUTH_22") (pintype "bidirectional"))
    )
    (net (code "69") (name "unconnected-(IC3-DB8{slash}DOUTB-Pad25)") (class "Default")
      (node (ref "IC3") (pin "25") (pinfunction "DB8/DOUTB_25") (pintype "bidirectional"))
    )
    (net (code "70") (name "unconnected-(IC3-DB9{slash}DOUTC-Pad27)") (class "Default")
      (node (ref "IC3") (pin "27") (pinfunction "DB9/DOUTC_27") (pintype "bidirectional"))
    )
    (net (code "71") (name "unconnected-(IC3-DB10{slash}DOUTD-Pad28)") (class "Default")
      (node (ref "IC3") (pin "28") (pinfunction "DB10/DOUTD_28") (pintype "bidirectional"))
    )
    (net (code "72") (name "unconnected-(IC3-FRSTDATA-Pad15)") (class "Default")
      (node (ref "IC3") (pin "15") (pinfunction "FRSTDATA_15") (pintype "bidirectional"))
    )
    (net (code "73") (name "unconnected-(IC3-~{WR}-Pad10)") (class "Default")
      (node (ref "IC3") (pin "10") (pinfunction "~{WR}_10") (pintype "bidirectional"))
    )
    (net (code "74") (name "unconnected-(IC5-PadNC)") (class "Default")
      (node (ref "IC5") (pin "NC") (pinfunction "NC_NC") (pintype "bidirectional"))
    )
    (net (code "75") (name "unconnected-(IC8-NC_1-Pad7)") (class "Default")
      (node (ref "IC8") (pin "7") (pinfunction "NC_1_7") (pintype "bidirectional"))
    )
    (net (code "76") (name "unconnected-(IC8-NC_2-Pad8)") (class "Default")
      (node (ref "IC8") (pin "8") (pinfunction "NC_2_8") (pintype "bidirectional"))
    )
    (net (code "77") (name "unconnected-(IC8-TP_1-Pad1)") (class "Default")
      (node (ref "IC8") (pin "1") (pinfunction "TP_1_1") (pintype "bidirectional"))
    )
    (net (code "78") (name "unconnected-(IC8-TP_2-Pad5)") (class "Default")
      (node (ref "IC8") (pin "5") (pinfunction "TP_2_5") (pintype "bidirectional"))
    )
    (net (code "79") (name "unconnected-(J3-Pad5)") (class "Default")
      (node (ref "J3") (pin "5") (pinfunction "5_5") (pintype "bidirectional"))
    )
    (net (code "80") (name "unconnected-(J3-Pad6)") (class "Default")
      (node (ref "J3") (pin "6") (pinfunction "6_6") (pintype "bidirectional"))
    )
    (net (code "81") (name "unconnected-(J3-Pad7)") (class "Default")
      (node (ref "J3") (pin "7") (pinfunction "7_7") (pintype "bidirectional"))
    )
    (net (code "82") (name "unconnected-(J3-Pad8)") (class "Default")
      (node (ref "J3") (pin "8") (pinfunction "8_8") (pintype "bidirectional"))
    )
    (net (code "83") (name "unconnected-(J4-Pad5)") (class "Default")
      (node (ref "J4") (pin "5") (pinfunction "5_5") (pintype "bidirectional"))
    )
    (net (code "84") (name "unconnected-(J4-Pad6)") (class "Default")
      (node (ref "J4") (pin "6") (pinfunction "6_6") (pintype "bidirectional"))
    )
    (net (code "85") (name "unconnected-(J4-Pad7)") (class "Default")
      (node (ref "J4") (pin "7") (pinfunction "7_7") (pintype "bidirectional"))
    )
    (net (code "86") (name "unconnected-(J4-Pad8)") (class "Default")
      (node (ref "J4") (pin "8") (pinfunction "8_8") (pintype "bidirectional"))
    )
    (net (code "87") (name "unconnected-(M1-10-Pad10{slash}CS)") (class "Default")
      (node (ref "M1") (pin "10/CS") (pinfunction "10_10/CS") (pintype "bidirectional"))
    )
    (net (code "88") (name "unconnected-(M1-16-Pad16{slash}A2)") (class "Default")
      (node (ref "M1") (pin "16/A2") (pinfunction "16_16/A2") (pintype "bidirectional"))
    )
    (net (code "89") (name "unconnected-(M1-17-Pad17{slash}A3)") (class "Default")
      (node (ref "M1") (pin "17/A3") (pinfunction "17_17/A3") (pintype "bidirectional"))
    )
    (net (code "90") (name "unconnected-(M1-20-Pad20{slash}A6)") (class "Default")
      (node (ref "M1") (pin "20/A6") (pinfunction "20_20/A6") (pintype "bidirectional"))
    )
    (net (code "91") (name "unconnected-(M1-21-Pad21{slash}A7)") (class "Default")
      (node (ref "M1") (pin "21/A7") (pinfunction "21_21/A7") (pintype "bidirectional"))
    )
    (net (code "92") (name "unconnected-(M1-22-Pad22{slash}A8)") (class "Default")
      (node (ref "M1") (pin "22/A8") (pinfunction "22_22/A8") (pintype "bidirectional"))
    )
    (net (code "93") (name "unconnected-(M1-23-Pad23{slash}A9)") (class "Default")
      (node (ref "M1") (pin "23/A9") (pinfunction "23_23/A9") (pintype "bidirectional"))
    )
    (net (code "94") (name "unconnected-(M1-31-Pad31{slash}A12)") (class "Default")
      (node (ref "M1") (pin "31/A12") (pinfunction "31_31/A12") (pintype "bidirectional"))
    )
    (net (code "95") (name "unconnected-(M1-Pad2)") (class "Default")
      (node (ref "M1") (pin "2") (pinfunction "2_2") (pintype "bidirectional"))
    )
    (net (code "96") (name "unconnected-(M1-Pad3)") (class "Default")
      (node (ref "M1") (pin "3") (pinfunction "3_3") (pintype "bidirectional"))
    )
    (net (code "97") (name "unconnected-(M1-Pad4)") (class "Default")
      (node (ref "M1") (pin "4") (pinfunction "4_4") (pintype "bidirectional"))
    )
    (net (code "98") (name "unconnected-(M1-Pad5)") (class "Default")
      (node (ref "M1") (pin "5") (pinfunction "5_5") (pintype "bidirectional"))
    )
    (net (code "99") (name "unconnected-(M1-Pad6)") (class "Default")
      (node (ref "M1") (pin "6") (pinfunction "6_6") (pintype "bidirectional"))
    )
    (net (code "100") (name "unconnected-(M1-Pad9)") (class "Default")
      (node (ref "M1") (pin "9") (pinfunction "9_9") (pintype "bidirectional"))
    )
    (net (code "101") (name "unconnected-(M1-Pad24)") (class "Default")
      (node (ref "M1") (pin "24") (pinfunction "24_24") (pintype "bidirectional"))
    )
    (net (code "102") (name "unconnected-(M1-Pad25)") (class "Default")
      (node (ref "M1") (pin "25") (pinfunction "25_25") (pintype "bidirectional"))
    )
    (net (code "103") (name "unconnected-(M1-Pad26)") (class "Default")
      (node (ref "M1") (pin "26") (pinfunction "26_26") (pintype "bidirectional"))
    )
    (net (code "104") (name "unconnected-(M1-Pad27)") (class "Default")
      (node (ref "M1") (pin "27") (pinfunction "27_27") (pintype "bidirectional"))
    )
    (net (code "105") (name "unconnected-(M1-Pad28)") (class "Default")
      (node (ref "M1") (pin "28") (pinfunction "28_28") (pintype "bidirectional"))
    )
    (net (code "106") (name "unconnected-(M1-Pad29)") (class "Default")
      (node (ref "M1") (pin "29") (pinfunction "29_29") (pintype "bidirectional"))
    )
    (net (code "107") (name "unconnected-(M1-Pad30)") (class "Default")
      (node (ref "M1") (pin "30") (pinfunction "30_30") (pintype "bidirectional"))
    )
    (net (code "108") (name "unconnected-(M1-Pad32)") (class "Default")
      (node (ref "M1") (pin "32") (pinfunction "32_32") (pintype "bidirectional"))
    )
    (net (code "109") (name "unconnected-(M1-Pad33)") (class "Default")
      (node (ref "M1") (pin "33") (pinfunction "33_33") (pintype "bidirectional"))
    )
    (net (code "110") (name "unconnected-(M1-Pad34)") (class "Default")
      (node (ref "M1") (pin "34") (pinfunction "34_34") (pintype "bidirectional"))
    )
    (net (code "111") (name "unconnected-(M1-Pad35)") (class "Default")
      (node (ref "M1") (pin "35") (pinfunction "35_35") (pintype "bidirectional"))
    )
    (net (code "112") (name "unconnected-(M1-Pad36)") (class "Default")
      (node (ref "M1") (pin "36") (pinfunction "36_36") (pintype "bidirectional"))
    )
    (net (code "113") (name "unconnected-(M1-Pad37)") (class "Default")
      (node (ref "M1") (pin "37") (pinfunction "37_37") (pintype "bidirectional"))
    )
    (net (code "114") (name "unconnected-(M1-Pad38)") (class "Default")
      (node (ref "M1") (pin "38") (pinfunction "38_38") (pintype "bidirectional"))
    )
    (net (code "115") (name "unconnected-(M1-Pad39)") (class "Default")
      (node (ref "M1") (pin "39") (pinfunction "39_39") (pintype "bidirectional"))
    )
  )
)
